# UserInterface.net
KiCad netlist of a schematic drawn in Altium Designer
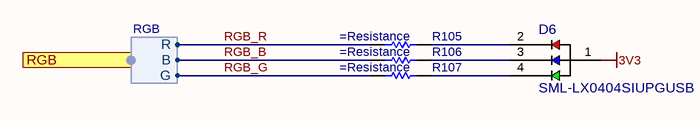
[diagram p0: UserInterface.SchDoc]

(export (version "E")
  (design (tool "Eeschema 10.0.6"))
  (components
    (comp (ref "D6")
      (value "SML-LX0404SIUPGUSB")
      (footprint "LED_SML-LX0404_LUM")
      (description "LED Tri-Color Blue/Green/Red 468nm/518nm/632nm 4-Pin SMD T/R")
      (fields (field (name "MANUFACTURER") "Lumex"))
      (libsource (lib "DiscreteSemiconductors") (part "SML-LX0404SIUPGUSB"))
    )
    (comp (ref "R105")
      (value "~")
      (footprint "R0402")
      (description "Res Thick Film 0402 680 Ohm 1% 0.063W(1/16W) ±100ppm/C Pad SMD T/R")
      (fields
        (field (name "MANUFACTURER") "Vishay")
        (field (name "MANUFACTURER PART NUMBER") "CRCW0402680RFKEDC")
      )
      (libsource (lib "Resistors") (part "RES0402-680-1%"))
    )
    (comp (ref "R106")
      (value "~")
      (footprint "R0402")
      (fields
        (field (name "MANUFACTURER") "Vishay")
        (field (name "MANUFACTURER PART NUMBER") "CRCW0402300RFKTD")
        (field (name "TOLERANCE") "1%")
      )
      (libsource (lib "Resistors") (part "RES0402-300-1%"))
    )
    (comp (ref "R107")
      (value "~")
      (footprint "R0402")
      (fields
        (field (name "MANUFACTURER") "Vishay")
        (field (name "MANUFACTURER PART NUMBER") "CRCW0402300RFKTD")
        (field (name "TOLERANCE") "1%")
      )
      (libsource (lib "Resistors") (part "RES0402-300-1%"))
    )
  )
  (nets
    (net (code "2") (name "/RGB_B") (class "Default")
      (node (ref "R106") (pin "1") (pinfunction "1_1") (pintype "passive"))
    )
    (net (code "3") (name "/RGB_G") (class "Default")
      (node (ref "R107") (pin "1") (pinfunction "1_1") (pintype "passive"))
    )
    (net (code "4") (name "/RGB_R") (class "Default")
      (node (ref "R105") (pin "1") (pinfunction "1_1") (pintype "passive"))
    )
    (net (code "6") (name "3V3") (class "Default")
      (node (ref "D6") (pin "1") (pinfunction "A_1") (pintype "passive"))
    )
    (net (code "7") (name "Net-(D6-B)") (class "Default")
      (node (ref "D6") (pin "3") (pinfunction "B_3") (pintype "passive"))
      (node (ref "R106") (pin "2") (pinfunction "2_2") (pintype "passive"))
    )
    (net (code "8") (name "Net-(D6-G)") (class "Default")
      (node (ref "D6") (pin "4") (pinfunction "G_4") (pintype "passive"))
      (node (ref "R107") (pin "2") (pinfunction "2_2") (pintype "passive"))
    )
    (net (code "9") (name "Net-(D6-R)") (class "Default")
      (node (ref "D6") (pin "2") (pinfunction "R_2") (pintype "passive"))
      (node (ref "R105") (pin "2") (pinfunction "2_2") (pintype "passive"))
    )
  )
)
